# 3w-rgb-led-connector-mk-4_0.net
KiCad netlist of a schematic drawn in EAGLE
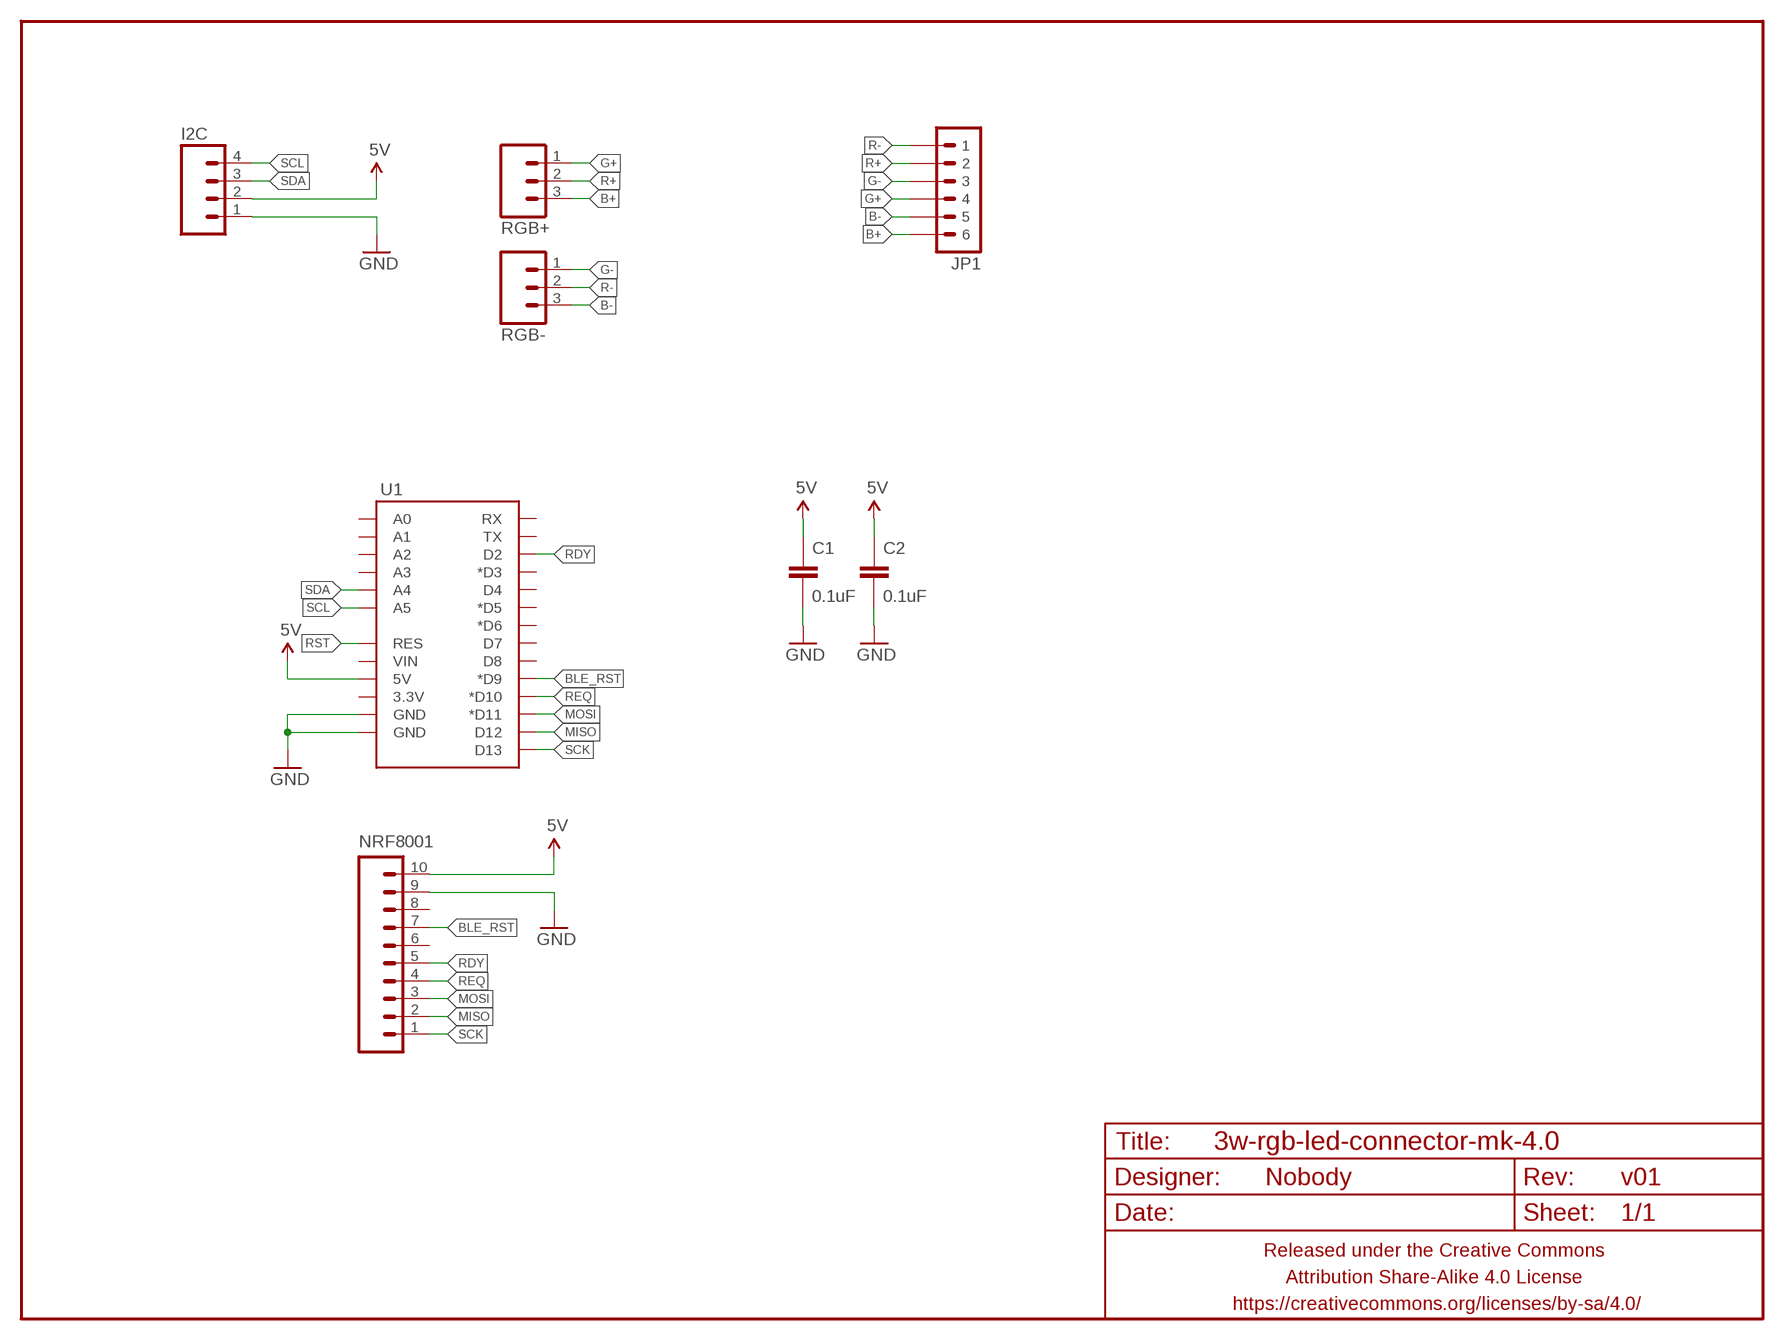
[diagram p0: schematic, sheet 1]

(export (version "E")
  (design (tool "Eeschema 10.0.6"))
  (components
    (comp (ref "C1")
      (value "0.1uF")
      (footprint "eagle-import:C025-024X044")
      (libsource (lib "eagle-import") (part "CAPACITOR-CERAMIC025-024X044"))
    )
    (comp (ref "C2")
      (value "0.1uF")
      (footprint "eagle-import:C025-024X044")
      (libsource (lib "eagle-import") (part "CAPACITOR-CERAMIC025-024X044"))
    )
    (comp (ref "FRAME1")
      (value "FRAME-LETTERNO_PACKAGE")
      (footprint "eagle-import:DUMMY")
      (fields (field (name "DESIGNER") "Nobody"))
      (libsource (lib "eagle-import") (part "FRAME-LETTERNO_PACKAGE"))
    )
    (comp (ref "I2C")
      (value "M04JST_XH_RA")
      (footprint "eagle-import:JST-4-XH-RA-PTH")
      (libsource (lib "eagle-import") (part "M04JST_XH_RA"))
    )
    (comp (ref "JP1")
      (value "M06JST-XH-RA-PTH-LONG")
      (footprint "eagle-import:1X06-2.5MM-JST-XH-RA-LONG")
      (libsource (lib "eagle-import") (part "M06JST-XH-RA-PTH-LONG"))
    )
    (comp (ref "NRF8001")
      (value "M10PTH-SLIM-ASS")
      (footprint "eagle-import:1X10_PTH_SLIMASS")
      (libsource (lib "eagle-import") (part "M10PTH-SLIM-ASS"))
    )
    (comp (ref "RGB+")
      (value "M03JST-3-XH-RA-PTH-LONG")
      (footprint "eagle-import:JST-3-XH-RA-PTH-LONG")
      (libsource (lib "eagle-import") (part "M03JST-3-XH-RA-PTH-LONG"))
    )
    (comp (ref "RGB-")
      (value "M03JST-3-XH-RA-PTH-LONG")
      (footprint "eagle-import:JST-3-XH-RA-PTH-LONG")
      (libsource (lib "eagle-import") (part "M03JST-3-XH-RA-PTH-LONG"))
    )
    (comp (ref "U1")
      (value "ARDUINO_SHIELD_SMALLER")
      (footprint "eagle-import:ARDUINO_SHIELD_NOOUTLINE_INSIDE_SMALLER")
      (libsource (lib "eagle-import") (part "ARDUINO_SHIELD_SMALLER"))
    )
  )
  (nets
    (net (code "1") (name "5V") (class "Default")
      (node (ref "C1") (pin "1") (pinfunction "1_1") (pintype "passive"))
      (node (ref "C2") (pin "1") (pinfunction "1_1") (pintype "passive"))
      (node (ref "I2C") (pin "2") (pinfunction "2_2") (pintype "passive"))
      (node (ref "NRF8001") (pin "10") (pinfunction "10_10") (pintype "passive"))
      (node (ref "U1") (pin "5V") (pinfunction "5V_5V") (pintype "bidirectional"))
    )
    (net (code "2") (name "B+") (class "Default")
      (node (ref "JP1") (pin "6") (pinfunction "6_6") (pintype "passive"))
      (node (ref "RGB+") (pin "3") (pinfunction "3_3") (pintype "passive"))
    )
    (net (code "3") (name "B-") (class "Default")
      (node (ref "JP1") (pin "5") (pinfunction "5_5") (pintype "passive"))
      (node (ref "RGB-") (pin "3") (pinfunction "3_3") (pintype "passive"))
    )
    (net (code "4") (name "BLE_RST") (class "Default")
      (node (ref "NRF8001") (pin "7") (pinfunction "7_7") (pintype "passive"))
      (node (ref "U1") (pin "D9") (pinfunction "*D9_D9") (pintype "bidirectional"))
    )
    (net (code "5") (name "G+") (class "Default")
      (node (ref "JP1") (pin "4") (pinfunction "4_4") (pintype "passive"))
      (node (ref "RGB+") (pin "1") (pinfunction "1_1") (pintype "passive"))
    )
    (net (code "6") (name "G-") (class "Default")
      (node (ref "JP1") (pin "3") (pinfunction "3_3") (pintype "passive"))
      (node (ref "RGB-") (pin "1") (pinfunction "1_1") (pintype "passive"))
    )
    (net (code "7") (name "GND") (class "Default")
      (node (ref "C1") (pin "2") (pinfunction "2_2") (pintype "passive"))
      (node (ref "C2") (pin "2") (pinfunction "2_2") (pintype "passive"))
      (node (ref "I2C") (pin "1") (pinfunction "1_1") (pintype "passive"))
      (node (ref "NRF8001") (pin "9") (pinfunction "9_9") (pintype "passive"))
      (node (ref "U1") (pin "GND@0") (pinfunction "GND_GND@0") (pintype "bidirectional"))
      (node (ref "U1") (pin "GND@1") (pinfunction "GND_GND@1") (pintype "bidirectional"))
    )
    (net (code "8") (name "MISO") (class "Default")
      (node (ref "NRF8001") (pin "2") (pinfunction "2_2") (pintype "passive"))
      (node (ref "U1") (pin "D12") (pinfunction "D12_D12") (pintype "bidirectional"))
    )
    (net (code "9") (name "MOSI") (class "Default")
      (node (ref "NRF8001") (pin "3") (pinfunction "3_3") (pintype "passive"))
      (node (ref "U1") (pin "D11") (pinfunction "*D11_D11") (pintype "bidirectional"))
    )
    (net (code "10") (name "R+") (class "Default")
      (node (ref "JP1") (pin "2") (pinfunction "2_2") (pintype "passive"))
      (node (ref "RGB+") (pin "2") (pinfunction "2_2") (pintype "passive"))
    )
    (net (code "11") (name "R-") (class "Default")
      (node (ref "JP1") (pin "1") (pinfunction "1_1") (pintype "passive"))
      (node (ref "RGB-") (pin "2") (pinfunction "2_2") (pintype "passive"))
    )
    (net (code "12") (name "RDY") (class "Default")
      (node (ref "NRF8001") (pin "5") (pinfunction "5_5") (pintype "passive"))
      (node (ref "U1") (pin "D2") (pinfunction "D2_D2") (pintype "bidirectional"))
    )
    (net (code "13") (name "REQ") (class "Default")
      (node (ref "NRF8001") (pin "4") (pinfunction "4_4") (pintype "passive"))
      (node (ref "U1") (pin "D10") (pinfunction "*D10_D10") (pintype "bidirectional"))
    )
    (net (code "14") (name "RST") (class "Default")
      (node (ref "U1") (pin "RES") (pinfunction "RES_RES") (pintype "bidirectional"))
    )
    (net (code "15") (name "SCK") (class "Default")
      (node (ref "NRF8001") (pin "1") (pinfunction "1_1") (pintype "passive"))
      (node (ref "U1") (pin "D13") (pinfunction "D13_D13") (pintype "bidirectional"))
    )
    (net (code "16") (name "SCL") (class "Default")
      (node (ref "I2C") (pin "4") (pinfunction "4_4") (pintype "passive"))
      (node (ref "U1") (pin "A5") (pinfunction "A5_A5") (pintype "bidirectional"))
    )
    (net (code "17") (name "SDA") (class "Default")
      (node (ref "I2C") (pin "3") (pinfunction "3_3") (pintype "passive"))
      (node (ref "U1") (pin "A4") (pinfunction "A4_A4") (pintype "bidirectional"))
    )
    (net (code "18") (name "unconnected-(NRF8001-Pad6)") (class "Default")
      (node (ref "NRF8001") (pin "6") (pinfunction "6_6") (pintype "passive"))
    )
    (net (code "19") (name "unconnected-(NRF8001-Pad8)") (class "Default")
      (node (ref "NRF8001") (pin "8") (pinfunction "8_8") (pintype "passive"))
    )
    (net (code "20") (name "unconnected-(U1-*D3-PadD3)") (class "Default")
      (node (ref "U1") (pin "D3") (pinfunction "*D3_D3") (pintype "bidirectional"))
    )
    (net (code "21") (name "unconnected-(U1-*D5-PadD5)") (class "Default")
      (node (ref "U1") (pin "D5") (pinfunction "*D5_D5") (pintype "bidirectional"))
    )
    (net (code "22") (name "unconnected-(U1-*D6-PadD6)") (class "Default")
      (node (ref "U1") (pin "D6") (pinfunction "*D6_D6") (pintype "bidirectional"))
    )
    (net (code "23") (name "unconnected-(U1-Pad3.3V)") (class "Default")
      (node (ref "U1") (pin "3.3V") (pinfunction "3.3V_3.3V") (pintype "bidirectional"))
    )
    (net (code "24") (name "unconnected-(U1-PadA0)") (class "Default")
      (node (ref "U1") (pin "A0") (pinfunction "A0_A0") (pintype "bidirectional"))
    )
    (net (code "25") (name "unconnected-(U1-PadA1)") (class "Default")
      (node (ref "U1") (pin "A1") (pinfunction "A1_A1") (pintype "bidirectional"))
    )
    (net (code "26") (name "unconnected-(U1-PadA2)") (class "Default")
      (node (ref "U1") (pin "A2") (pinfunction "A2_A2") (pintype "bidirectional"))
    )
    (net (code "27") (name "unconnected-(U1-PadA3)") (class "Default")
      (node (ref "U1") (pin "A3") (pinfunction "A3_A3") (pintype "bidirectional"))
    )
    (net (code "28") (name "unconnected-(U1-PadD4)") (class "Default")
      (node (ref "U1") (pin "D4") (pinfunction "D4_D4") (pintype "bidirectional"))
    )
    (net (code "29") (name "unconnected-(U1-PadD7)") (class "Default")
      (node (ref "U1") (pin "D7") (pinfunction "D7_D7") (pintype "bidirectional"))
    )
    (net (code "30") (name "unconnected-(U1-PadD8)") (class "Default")
      (node (ref "U1") (pin "D8") (pinfunction "D8_D8") (pintype "bidirectional"))
    )
    (net (code "31") (name "unconnected-(U1-PadRX)") (class "Default")
      (node (ref "U1") (pin "RX") (pinfunction "RX_RX") (pintype "bidirectional"))
    )
    (net (code "32") (name "unconnected-(U1-PadTX)") (class "Default")
      (node (ref "U1") (pin "TX") (pinfunction "TX_TX") (pintype "bidirectional"))
    )
    (net (code "33") (name "unconnected-(U1-PadVIN)") (class "Default")
      (node (ref "U1") (pin "VIN") (pinfunction "VIN_VIN") (pintype "bidirectional"))
    )
  )
)
